# MSi001_board.net
KiCad netlist of a schematic drawn in EAGLE
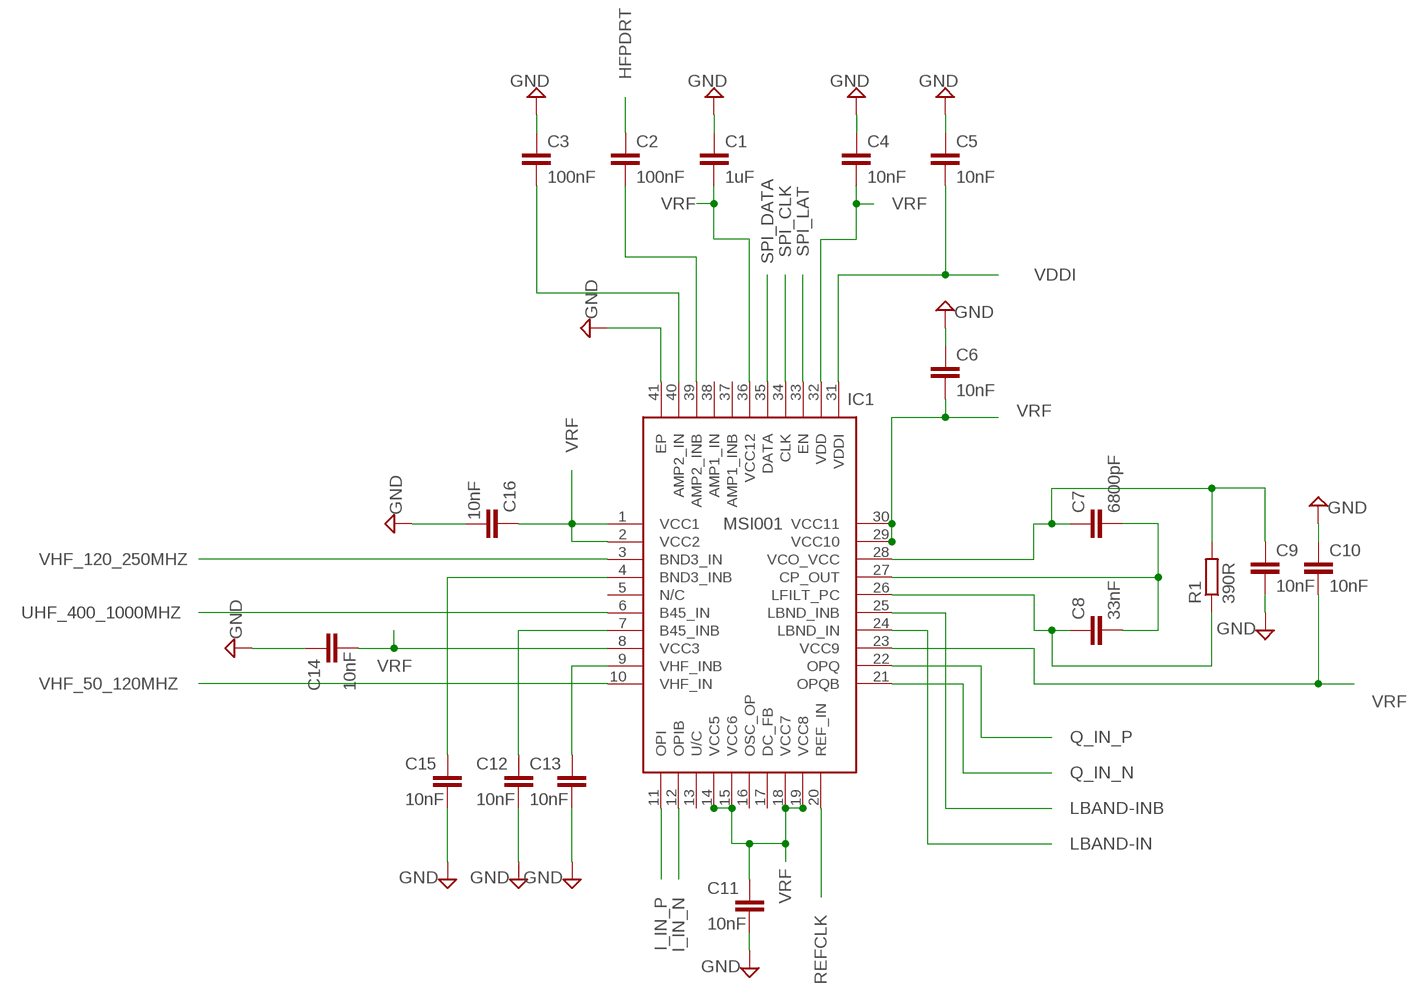
[diagram p0: schematic, sheet 1, part 1 of 2]
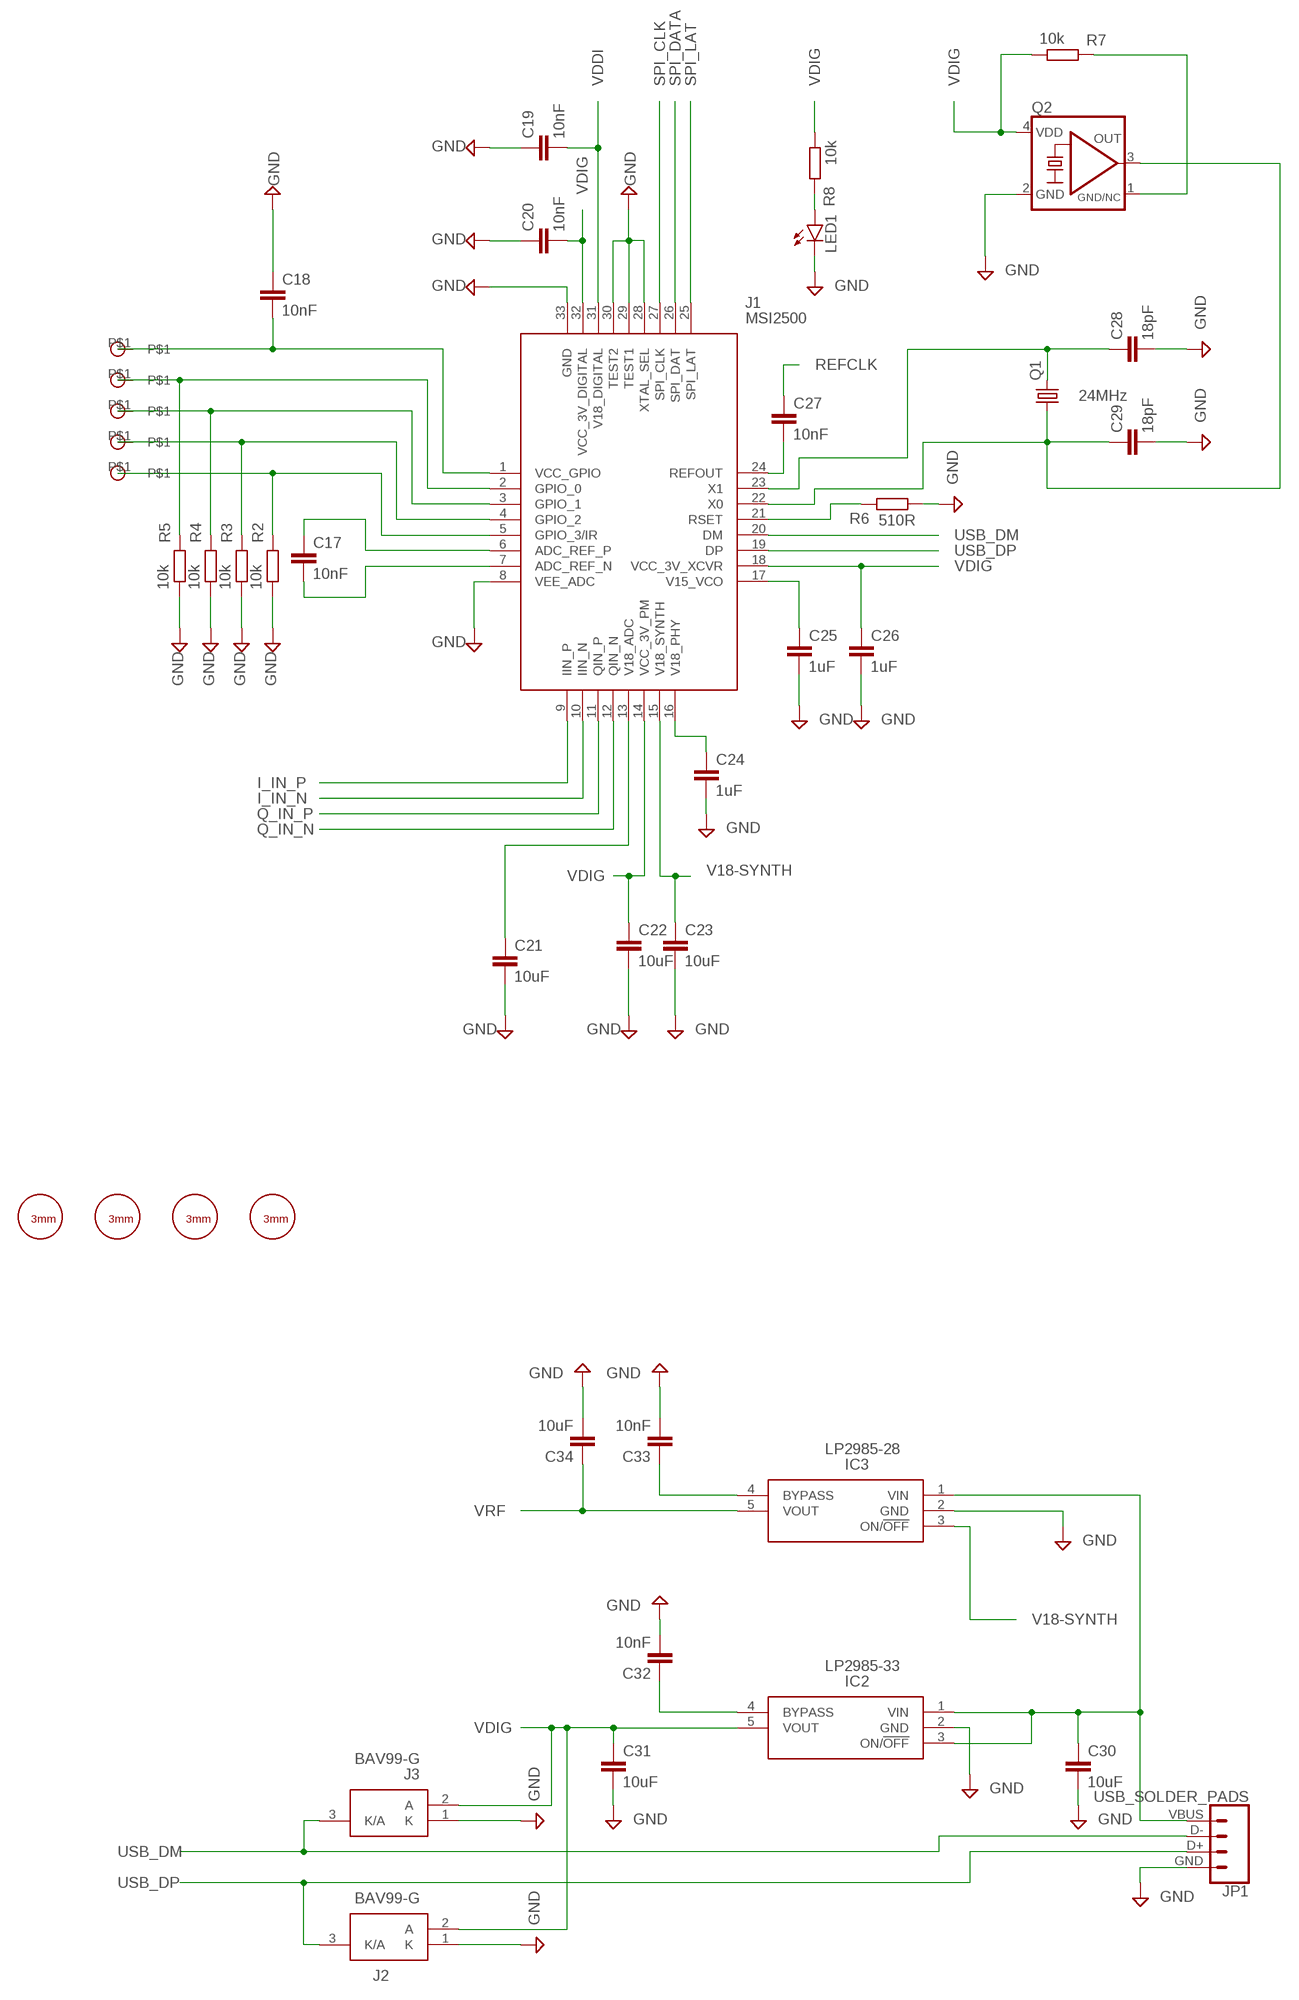
[diagram p1: schematic, sheet 1, part 2 of 2]

(export (version "E")
  (design (tool "Eeschema 10.0.6"))
  (components
    (comp (ref "C1")
      (value "1uF")
      (footprint "eagle-import:C0805K")
      (libsource (lib "eagle-import") (part "C-EUC0805K"))
    )
    (comp (ref "C2")
      (value "100nF")
      (footprint "eagle-import:C0603K")
      (libsource (lib "eagle-import") (part "C-EUC0603K"))
    )
    (comp (ref "C3")
      (value "100nF")
      (footprint "eagle-import:C0603K")
      (libsource (lib "eagle-import") (part "C-EUC0603K"))
    )
    (comp (ref "C4")
      (value "10nF")
      (footprint "eagle-import:C0603K")
      (libsource (lib "eagle-import") (part "C-EUC0603K"))
    )
    (comp (ref "C5")
      (value "10nF")
      (footprint "eagle-import:C0603K")
      (libsource (lib "eagle-import") (part "C-EUC0603K"))
    )
    (comp (ref "C6")
      (value "10nF")
      (footprint "eagle-import:C0603K")
      (libsource (lib "eagle-import") (part "C-EUC0603K"))
    )
    (comp (ref "C7")
      (value "6800pF")
      (footprint "eagle-import:C0603K")
      (libsource (lib "eagle-import") (part "C-EUC0603K"))
    )
    (comp (ref "C8")
      (value "33nF")
      (footprint "eagle-import:C0603K")
      (libsource (lib "eagle-import") (part "C-EUC0603K"))
    )
    (comp (ref "C9")
      (value "10nF")
      (footprint "eagle-import:C0603K")
      (libsource (lib "eagle-import") (part "C-EUC0603K"))
    )
    (comp (ref "C10")
      (value "10nF")
      (footprint "eagle-import:C0603K")
      (libsource (lib "eagle-import") (part "C-EUC0603K"))
    )
    (comp (ref "C11")
      (value "10nF")
      (footprint "eagle-import:C0603K")
      (libsource (lib "eagle-import") (part "C-EUC0603K"))
    )
    (comp (ref "C12")
      (value "10nF")
      (footprint "eagle-import:C0603K")
      (libsource (lib "eagle-import") (part "C-EUC0603K"))
    )
    (comp (ref "C13")
      (value "10nF")
      (footprint "eagle-import:C0603K")
      (libsource (lib "eagle-import") (part "C-EUC0603K"))
    )
    (comp (ref "C14")
      (value "10nF")
      (footprint "eagle-import:C0603K")
      (libsource (lib "eagle-import") (part "C-EUC0603K"))
    )
    (comp (ref "C15")
      (value "10nF")
      (footprint "eagle-import:C0603K")
      (libsource (lib "eagle-import") (part "C-EUC0603K"))
    )
    (comp (ref "C16")
      (value "10nF")
      (footprint "eagle-import:C0603K")
      (libsource (lib "eagle-import") (part "C-EUC0603K"))
    )
    (comp (ref "C17")
      (value "10nF")
      (footprint "eagle-import:C0603K")
      (libsource (lib "eagle-import") (part "C-EUC0603K"))
    )
    (comp (ref "C18")
      (value "10nF")
      (footprint "eagle-import:C0603K")
      (libsource (lib "eagle-import") (part "C-EUC0603K"))
    )
    (comp (ref "C19")
      (value "10nF")
      (footprint "eagle-import:C0603K")
      (libsource (lib "eagle-import") (part "C-EUC0603K"))
    )
    (comp (ref "C20")
      (value "10nF")
      (footprint "eagle-import:C0603K")
      (libsource (lib "eagle-import") (part "C-EUC0603K"))
    )
    (comp (ref "C21")
      (value "10uF")
      (footprint "eagle-import:C0805K")
      (libsource (lib "eagle-import") (part "C-EUC0805K"))
    )
    (comp (ref "C22")
      (value "10uF")
      (footprint "eagle-import:C0805K")
      (libsource (lib "eagle-import") (part "C-EUC0805K"))
    )
    (comp (ref "C23")
      (value "10uF")
      (footprint "eagle-import:C0805K")
      (libsource (lib "eagle-import") (part "C-EUC0805K"))
    )
    (comp (ref "C24")
      (value "1uF")
      (footprint "eagle-import:C0805K")
      (libsource (lib "eagle-import") (part "C-EUC0805K"))
    )
    (comp (ref "C25")
      (value "1uF")
      (footprint "eagle-import:C0805K")
      (libsource (lib "eagle-import") (part "C-EUC0805K"))
    )
    (comp (ref "C26")
      (value "1uF")
      (footprint "eagle-import:C0805K")
      (libsource (lib "eagle-import") (part "C-EUC0805K"))
    )
    (comp (ref "C27")
      (value "10nF")
      (footprint "eagle-import:C0603K")
      (libsource (lib "eagle-import") (part "C-EUC0603K"))
    )
    (comp (ref "C28")
      (value "18pF")
      (footprint "eagle-import:C0603K")
      (libsource (lib "eagle-import") (part "C-EUC0603K"))
    )
    (comp (ref "C29")
      (value "18pF")
      (footprint "eagle-import:C0603K")
      (libsource (lib "eagle-import") (part "C-EUC0603K"))
    )
    (comp (ref "C30")
      (value "10uF")
      (footprint "eagle-import:C0805K")
      (libsource (lib "eagle-import") (part "C-EUC0805K"))
    )
    (comp (ref "C31")
      (value "10uF")
      (footprint "eagle-import:C0805K")
      (libsource (lib "eagle-import") (part "C-EUC0805K"))
    )
    (comp (ref "C32")
      (value "10nF")
      (footprint "eagle-import:C0603K")
      (libsource (lib "eagle-import") (part "C-EUC0603K"))
    )
    (comp (ref "C33")
      (value "10nF")
      (footprint "eagle-import:C0603K")
      (libsource (lib "eagle-import") (part "C-EUC0603K"))
    )
    (comp (ref "C34")
      (value "10uF")
      (footprint "eagle-import:C0805K")
      (libsource (lib "eagle-import") (part "C-EUC0805K"))
    )
    (comp (ref "IC1")
      (value "MSI001")
      (footprint "eagle-import:QFN50P600X600X90-41N")
      (libsource (lib "eagle-import") (part "MSI001"))
    )
    (comp (ref "IC2")
      (value "LP2985-33")
      (footprint "eagle-import:SOT95P280X145-5N")
      (fields
        (field (name "ARROW_PART_NUMBER") "LP2985-30DBVR")
        (field (name "MOUSER_PART_NUMBER") "595-LP2985-30DBVR")
      )
      (libsource (lib "eagle-import") (part "LP2985-30DBVR"))
    )
    (comp (ref "IC3")
      (value "LP2985-28")
      (footprint "eagle-import:SOT95P280X145-5N")
      (fields
        (field (name "ARROW_PART_NUMBER") "LP2985-30DBVR")
        (field (name "MOUSER_PART_NUMBER") "595-LP2985-30DBVR")
      )
      (libsource (lib "eagle-import") (part "LP2985-30DBVR"))
    )
    (comp (ref "J1")
      (value "MSI2500")
      (footprint "eagle-import:QFN50P500X500X90-33N")
      (libsource (lib "eagle-import") (part "MSI2500"))
    )
    (comp (ref "J2")
      (value "BAV99-G")
      (footprint "eagle-import:SOT97P230X110-3N")
      (libsource (lib "eagle-import") (part "BAV99-G"))
    )
    (comp (ref "J3")
      (value "BAV99-G")
      (footprint "eagle-import:SOT97P230X110-3N")
      (libsource (lib "eagle-import") (part "BAV99-G"))
    )
    (comp (ref "JP1")
      (value "USB_SOLDER_PADS")
      (footprint "eagle-import:USB-SOLDER-PADS")
      (libsource (lib "eagle-import") (part "USB_SOLDER_PADS"))
    )
    (comp (ref "LED1")
      (value "LEDCHIPLED_0805")
      (footprint "eagle-import:CHIPLED_0805")
      (libsource (lib "eagle-import") (part "LEDCHIPLED_0805"))
    )
    (comp (ref "Q1")
      (value "24MHz")
      (footprint "eagle-import:HC49_S")
      (libsource (lib "eagle-import") (part "CRYSTALHC49S"))
    )
    (comp (ref "Q2")
      (value "KXO-TCXO-CMOS-83")
      (footprint "eagle-import:5.0X3.2_KXO-83-TCXO")
      (libsource (lib "eagle-import") (part "KXO-TCXO-CMOS-83"))
    )
    (comp (ref "R1")
      (value "390R")
      (footprint "eagle-import:R0603")
      (libsource (lib "eagle-import") (part "R-EU_R0603"))
    )
    (comp (ref "R2")
      (value "10k")
      (footprint "eagle-import:R0603")
      (libsource (lib "eagle-import") (part "R-EU_R0603"))
    )
    (comp (ref "R3")
      (value "10k")
      (footprint "eagle-import:R0603")
      (libsource (lib "eagle-import") (part "R-EU_R0603"))
    )
    (comp (ref "R4")
      (value "10k")
      (footprint "eagle-import:R0603")
      (libsource (lib "eagle-import") (part "R-EU_R0603"))
    )
    (comp (ref "R5")
      (value "10k")
      (footprint "eagle-import:R0603")
      (libsource (lib "eagle-import") (part "R-EU_R0603"))
    )
    (comp (ref "R6")
      (value "510R")
      (footprint "eagle-import:R0603")
      (libsource (lib "eagle-import") (part "R-EU_R0603"))
    )
    (comp (ref "R7")
      (value "10k")
      (footprint "eagle-import:R0603")
      (libsource (lib "eagle-import") (part "R-EU_R0603"))
    )
    (comp (ref "R8")
      (value "10k")
      (footprint "eagle-import:R0603")
      (libsource (lib "eagle-import") (part "R-EU_R0603"))
    )
    (comp (ref "U$1")
      (value "3MM_HOLE")
      (footprint "eagle-import:3MM_HOLE")
      (libsource (lib "eagle-import") (part "3MM_HOLE"))
    )
    (comp (ref "U$2")
      (value "SMD_PIN")
      (footprint "eagle-import:SMD_PIN")
      (libsource (lib "eagle-import") (part "SMD_PIN"))
    )
    (comp (ref "U$3")
      (value "SMD_PIN")
      (footprint "eagle-import:SMD_PIN")
      (libsource (lib "eagle-import") (part "SMD_PIN"))
    )
    (comp (ref "U$4")
      (value "SMD_PIN")
      (footprint "eagle-import:SMD_PIN")
      (libsource (lib "eagle-import") (part "SMD_PIN"))
    )
    (comp (ref "U$5")
      (value "SMD_PIN")
      (footprint "eagle-import:SMD_PIN")
      (libsource (lib "eagle-import") (part "SMD_PIN"))
    )
    (comp (ref "U$6")
      (value "3MM_HOLE")
      (footprint "eagle-import:3MM_HOLE")
      (libsource (lib "eagle-import") (part "3MM_HOLE"))
    )
    (comp (ref "U$7")
      (value "3MM_HOLE")
      (footprint "eagle-import:3MM_HOLE")
      (libsource (lib "eagle-import") (part "3MM_HOLE"))
    )
    (comp (ref "U$8")
      (value "3MM_HOLE")
      (footprint "eagle-import:3MM_HOLE")
      (libsource (lib "eagle-import") (part "3MM_HOLE"))
    )
    (comp (ref "VCC_GPIO")
      (value "SMD_PIN")
      (footprint "eagle-import:SMD_PIN")
      (libsource (lib "eagle-import") (part "SMD_PIN"))
    )
  )
  (nets
    (net (code "1") (name "/HFPDRT") (class "Default")
      (node (ref "C2") (pin "1") (pinfunction "1_1") (pintype "passive"))
    )
    (net (code "2") (name "/I_IN_N") (class "Default")
      (node (ref "IC1") (pin "12") (pinfunction "OPIB_12") (pintype "bidirectional"))
      (node (ref "J1") (pin "10") (pinfunction "IIN_N_10") (pintype "bidirectional"))
    )
    (net (code "3") (name "/I_IN_P") (class "Default")
      (node (ref "IC1") (pin "11") (pinfunction "OPI_11") (pintype "bidirectional"))
      (node (ref "J1") (pin "9") (pinfunction "IIN_P_9") (pintype "bidirectional"))
    )
    (net (code "4") (name "/LBAND-IN") (class "Default")
      (node (ref "IC1") (pin "24") (pinfunction "LBND_IN_24") (pintype "bidirectional"))
    )
    (net (code "5") (name "/LBAND-INB") (class "Default")
      (node (ref "IC1") (pin "25") (pinfunction "LBND_INB_25") (pintype "bidirectional"))
    )
    (net (code "6") (name "/Q_IN_N") (class "Default")
      (node (ref "IC1") (pin "21") (pinfunction "OPQB_21") (pintype "bidirectional"))
      (node (ref "J1") (pin "12") (pinfunction "QIN_N_12") (pintype "bidirectional"))
    )
    (net (code "7") (name "/Q_IN_P") (class "Default")
      (node (ref "IC1") (pin "22") (pinfunction "OPQ_22") (pintype "bidirectional"))
      (node (ref "J1") (pin "11") (pinfunction "QIN_P_11") (pintype "bidirectional"))
    )
    (net (code "8") (name "/REFCLK") (class "Default")
      (node (ref "C27") (pin "1") (pinfunction "1_1") (pintype "passive"))
      (node (ref "IC1") (pin "20") (pinfunction "REF_IN_20") (pintype "bidirectional"))
    )
    (net (code "9") (name "/SPI_CLK") (class "Default")
      (node (ref "IC1") (pin "34") (pinfunction "CLK_34") (pintype "bidirectional"))
      (node (ref "J1") (pin "27") (pinfunction "SPI_CLK_27") (pintype "bidirectional"))
    )
    (net (code "10") (name "/SPI_DATA") (class "Default")
      (node (ref "IC1") (pin "35") (pinfunction "DATA_35") (pintype "bidirectional"))
      (node (ref "J1") (pin "26") (pinfunction "SPI_DAT_26") (pintype "bidirectional"))
    )
    (net (code "11") (name "/SPI_LAT") (class "Default")
      (node (ref "IC1") (pin "33") (pinfunction "EN_33") (pintype "bidirectional"))
      (node (ref "J1") (pin "25") (pinfunction "SPI_LAT_25") (pintype "bidirectional"))
    )
    (net (code "12") (name "/UHF_400_1000MHZ") (class "Default")
      (node (ref "IC1") (pin "6") (pinfunction "B45_IN_6") (pintype "bidirectional"))
    )
    (net (code "13") (name "/USB_DM") (class "Default")
      (node (ref "J1") (pin "20") (pinfunction "DM_20") (pintype "bidirectional"))
      (node (ref "J3") (pin "3") (pinfunction "K/A_3") (pintype "bidirectional"))
      (node (ref "JP1") (pin "D-") (pinfunction "2_D-") (pintype "passive"))
    )
    (net (code "14") (name "/USB_DP") (class "Default")
      (node (ref "J1") (pin "19") (pinfunction "DP_19") (pintype "bidirectional"))
      (node (ref "J2") (pin "3") (pinfunction "K/A_3") (pintype "bidirectional"))
      (node (ref "JP1") (pin "D+") (pinfunction "3_D+") (pintype "passive"))
    )
    (net (code "15") (name "/V18-SYNTH") (class "Default")
      (node (ref "C23") (pin "1") (pinfunction "1_1") (pintype "passive"))
      (node (ref "IC3") (pin "3") (pinfunction "ON/~{OFF}_3") (pintype "bidirectional"))
      (node (ref "J1") (pin "15") (pinfunction "V18_SYNTH_15") (pintype "bidirectional"))
    )
    (net (code "16") (name "/VDDI") (class "Default")
      (node (ref "C19") (pin "2") (pinfunction "2_2") (pintype "passive"))
      (node (ref "C5") (pin "2") (pinfunction "2_2") (pintype "passive"))
      (node (ref "IC1") (pin "31") (pinfunction "VDDI_31") (pintype "bidirectional"))
      (node (ref "J1") (pin "31") (pinfunction "V18_DIGITAL_31") (pintype "bidirectional"))
    )
    (net (code "17") (name "/VDIG") (class "Default")
      (node (ref "C20") (pin "2") (pinfunction "2_2") (pintype "passive"))
      (node (ref "C22") (pin "1") (pinfunction "1_1") (pintype "passive"))
      (node (ref "C26") (pin "1") (pinfunction "1_1") (pintype "passive"))
      (node (ref "C31") (pin "1") (pinfunction "1_1") (pintype "passive"))
      (node (ref "IC2") (pin "5") (pinfunction "VOUT_5") (pintype "bidirectional"))
      (node (ref "J1") (pin "14") (pinfunction "VCC_3V_PM_14") (pintype "bidirectional"))
      (node (ref "J1") (pin "18") (pinfunction "VCC_3V_XCVR_18") (pintype "bidirectional"))
      (node (ref "J1") (pin "32") (pinfunction "VCC_3V_DIGITAL_32") (pintype "bidirectional"))
      (node (ref "J2") (pin "2") (pinfunction "A_2") (pintype "bidirectional"))
      (node (ref "J3") (pin "2") (pinfunction "A_2") (pintype "bidirectional"))
      (node (ref "Q2") (pin "4") (pinfunction "VDD_4") (pintype "power_in"))
      (node (ref "R7") (pin "1") (pinfunction "1_1") (pintype "passive"))
      (node (ref "R8") (pin "1") (pinfunction "1_1") (pintype "passive"))
    )
    (net (code "18") (name "/VHF_50_120MHZ") (class "Default")
      (node (ref "IC1") (pin "10") (pinfunction "VHF_IN_10") (pintype "bidirectional"))
    )
    (net (code "19") (name "/VHF_120_250MHZ") (class "Default")
      (node (ref "IC1") (pin "3") (pinfunction "BND3_IN_3") (pintype "bidirectional"))
    )
    (net (code "20") (name "/VRF") (class "Default")
      (node (ref "C1") (pin "2") (pinfunction "2_2") (pintype "passive"))
      (node (ref "C10") (pin "2") (pinfunction "2_2") (pintype "passive"))
      (node (ref "C11") (pin "1") (pinfunction "1_1") (pintype "passive"))
      (node (ref "C14") (pin "2") (pinfunction "2_2") (pintype "passive"))
      (node (ref "C16") (pin "1") (pinfunction "1_1") (pintype "passive"))
      (node (ref "C34") (pin "1") (pinfunction "1_1") (pintype "passive"))
      (node (ref "C4") (pin "2") (pinfunction "2_2") (pintype "passive"))
      (node (ref "C6") (pin "2") (pinfunction "2_2") (pintype "passive"))
      (node (ref "IC1") (pin "1") (pinfunction "VCC1_1") (pintype "bidirectional"))
      (node (ref "IC1") (pin "14") (pinfunction "VCC5_14") (pintype "bidirectional"))
      (node (ref "IC1") (pin "15") (pinfunction "VCC6_15") (pintype "bidirectional"))
      (node (ref "IC1") (pin "18") (pinfunction "VCC7_18") (pintype "bidirectional"))
      (node (ref "IC1") (pin "19") (pinfunction "VCC8_19") (pintype "bidirectional"))
      (node (ref "IC1") (pin "2") (pinfunction "VCC2_2") (pintype "bidirectional"))
      (node (ref "IC1") (pin "23") (pinfunction "VCC9_23") (pintype "bidirectional"))
      (node (ref "IC1") (pin "29") (pinfunction "VCC10_29") (pintype "bidirectional"))
      (node (ref "IC1") (pin "30") (pinfunction "VCC11_30") (pintype "bidirectional"))
      (node (ref "IC1") (pin "32") (pinfunction "VDD_32") (pintype "bidirectional"))
      (node (ref "IC1") (pin "36") (pinfunction "VCC12_36") (pintype "bidirectional"))
      (node (ref "IC1") (pin "8") (pinfunction "VCC3_8") (pintype "bidirectional"))
      (node (ref "IC3") (pin "5") (pinfunction "VOUT_5") (pintype "bidirectional"))
    )
    (net (code "21") (name "GND") (class "Default")
      (node (ref "C1") (pin "1") (pinfunction "1_1") (pintype "passive"))
      (node (ref "C10") (pin "1") (pinfunction "1_1") (pintype "passive"))
      (node (ref "C11") (pin "2") (pinfunction "2_2") (pintype "passive"))
      (node (ref "C12") (pin "2") (pinfunction "2_2") (pintype "passive"))
      (node (ref "C13") (pin "2") (pinfunction "2_2") (pintype "passive"))
      (node (ref "C14") (pin "1") (pinfunction "1_1") (pintype "passive"))
      (node (ref "C15") (pin "2") (pinfunction "2_2") (pintype "passive"))
      (node (ref "C16") (pin "2") (pinfunction "2_2") (pintype "passive"))
      (node (ref "C18") (pin "1") (pinfunction "1_1") (pintype "passive"))
      (node (ref "C19") (pin "1") (pinfunction "1_1") (pintype "passive"))
      (node (ref "C20") (pin "1") (pinfunction "1_1") (pintype "passive"))
      (node (ref "C21") (pin "2") (pinfunction "2_2") (pintype "passive"))
      (node (ref "C22") (pin "2") (pinfunction "2_2") (pintype "passive"))
      (node (ref "C23") (pin "2") (pinfunction "2_2") (pintype "passive"))
      (node (ref "C24") (pin "2") (pinfunction "2_2") (pintype "passive"))
      (node (ref "C25") (pin "2") (pinfunction "2_2") (pintype "passive"))
      (node (ref "C26") (pin "2") (pinfunction "2_2") (pintype "passive"))
      (node (ref "C28") (pin "2") (pinfunction "2_2") (pintype "passive"))
      (node (ref "C29") (pin "2") (pinfunction "2_2") (pintype "passive"))
      (node (ref "C3") (pin "1") (pinfunction "1_1") (pintype "passive"))
      (node (ref "C30") (pin "2") (pinfunction "2_2") (pintype "passive"))
      (node (ref "C31") (pin "2") (pinfunction "2_2") (pintype "passive"))
      (node (ref "C32") (pin "2") (pinfunction "2_2") (pintype "passive"))
      (node (ref "C33") (pin "2") (pinfunction "2_2") (pintype "passive"))
      (node (ref "C34") (pin "2") (pinfunction "2_2") (pintype "passive"))
      (node (ref "C4") (pin "1") (pinfunction "1_1") (pintype "passive"))
      (node (ref "C5") (pin "1") (pinfunction "1_1") (pintype "passive"))
      (node (ref "C6") (pin "1") (pinfunction "1_1") (pintype "passive"))
      (node (ref "C9") (pin "2") (pinfunction "2_2") (pintype "passive"))
      (node (ref "IC1") (pin "41") (pinfunction "EP_41") (pintype "bidirectional"))
      (node (ref "IC2") (pin "2") (pinfunction "GND_2") (pintype "bidirectional"))
      (node (ref "IC3") (pin "2") (pinfunction "GND_2") (pintype "bidirectional"))
      (node (ref "J1") (pin "28") (pinfunction "XTAL_SEL_28") (pintype "bidirectional"))
      (node (ref "J1") (pin "29") (pinfunction "TEST1_29") (pintype "bidirectional"))
      (node (ref "J1") (pin "30") (pinfunction "TEST2_30") (pintype "bidirectional"))
      (node (ref "J1") (pin "33") (pinfunction "GND_33") (pintype "bidirectional"))
      (node (ref "J1") (pin "8") (pinfunction "VEE_ADC_8") (pintype "bidirectional"))
      (node (ref "J2") (pin "1") (pinfunction "K_1") (pintype "bidirectional"))
      (node (ref "J3") (pin "1") (pinfunction "K_1") (pintype "bidirectional"))
      (node (ref "JP1") (pin "GND") (pinfunction "4_GND") (pintype "passive"))
      (node (ref "LED1") (pin "C") (pinfunction "C_C") (pintype "passive"))
      (node (ref "Q2") (pin "2") (pinfunction "GND_2") (pintype "power_in"))
      (node (ref "R2") (pin "1") (pinfunction "1_1") (pintype "passive"))
      (node (ref "R3") (pin "1") (pinfunction "1_1") (pintype "passive"))
      (node (ref "R4") (pin "1") (pinfunction "1_1") (pintype "passive"))
      (node (ref "R5") (pin "1") (pinfunction "1_1") (pintype "passive"))
      (node (ref "R6") (pin "1") (pinfunction "1_1") (pintype "passive"))
    )
    (net (code "22") (name "Net-(IC1-AMP2_IN)") (class "Default")
      (node (ref "C3") (pin "2") (pinfunction "2_2") (pintype "passive"))
      (node (ref "IC1") (pin "40") (pinfunction "AMP2_IN_40") (pintype "bidirectional"))
    )
    (net (code "23") (name "Net-(IC1-AMP2_INB)") (class "Default")
      (node (ref "C2") (pin "2") (pinfunction "2_2") (pintype "passive"))
      (node (ref "IC1") (pin "39") (pinfunction "AMP2_INB_39") (pintype "bidirectional"))
    )
    (net (code "24") (name "Net-(IC1-B45_INB)") (class "Default")
      (node (ref "C12") (pin "1") (pinfunction "1_1") (pintype "passive"))
      (node (ref "IC1") (pin "7") (pinfunction "B45_INB_7") (pintype "bidirectional"))
    )
    (net (code "25") (name "Net-(IC1-BND3_INB)") (class "Default")
      (node (ref "C15") (pin "1") (pinfunction "1_1") (pintype "passive"))
      (node (ref "IC1") (pin "4") (pinfunction "BND3_INB_4") (pintype "bidirectional"))
    )
    (net (code "26") (name "Net-(IC1-CP_OUT)") (class "Default")
      (node (ref "C7") (pin "2") (pinfunction "2_2") (pintype "passive"))
      (node (ref "C8") (pin "2") (pinfunction "2_2") (pintype "passive"))
      (node (ref "IC1") (pin "27") (pinfunction "CP_OUT_27") (pintype "bidirectional"))
    )
    (net (code "27") (name "Net-(IC1-LFILT_PC)") (class "Default")
      (node (ref "C8") (pin "1") (pinfunction "1_1") (pintype "passive"))
      (node (ref "IC1") (pin "26") (pinfunction "LFILT_PC_26") (pintype "bidirectional"))
      (node (ref "R1") (pin "1") (pinfunction "1_1") (pintype "passive"))
    )
    (net (code "28") (name "Net-(IC1-VCO_VCC)") (class "Default")
      (node (ref "C7") (pin "1") (pinfunction "1_1") (pintype "passive"))
      (node (ref "C9") (pin "1") (pinfunction "1_1") (pintype "passive"))
      (node (ref "IC1") (pin "28") (pinfunction "VCO_VCC_28") (pintype "bidirectional"))
      (node (ref "R1") (pin "2") (pinfunction "2_2") (pintype "passive"))
    )
    (net (code "29") (name "Net-(IC1-VHF_INB)") (class "Default")
      (node (ref "C13") (pin "1") (pinfunction "1_1") (pintype "passive"))
      (node (ref "IC1") (pin "9") (pinfunction "VHF_INB_9") (pintype "bidirectional"))
    )
    (net (code "30") (name "Net-(IC2-BYPASS)") (class "Default")
      (node (ref "C32") (pin "1") (pinfunction "1_1") (pintype "passive"))
      (node (ref "IC2") (pin "4") (pinfunction "BYPASS_4") (pintype "bidirectional"))
    )
    (net (code "31") (name "Net-(IC2-ON{slash}~{OFF})") (class "Default")
      (node (ref "C30") (pin "1") (pinfunction "1_1") (pintype "passive"))
      (node (ref "IC2") (pin "1") (pinfunction "VIN_1") (pintype "bidirectional"))
      (node (ref "IC2") (pin "3") (pinfunction "ON/~{OFF}_3") (pintype "bidirectional"))
      (node (ref "IC3") (pin "1") (pinfunction "VIN_1") (pintype "bidirectional"))
      (node (ref "JP1") (pin "VBUS") (pinfunction "1_VBUS") (pintype "passive"))
    )
    (net (code "32") (name "Net-(IC3-BYPASS)") (class "Default")
      (node (ref "C33") (pin "1") (pinfunction "1_1") (pintype "passive"))
      (node (ref "IC3") (pin "4") (pinfunction "BYPASS_4") (pintype "bidirectional"))
    )
    (net (code "33") (name "Net-(J1-ADC_REF_N)") (class "Default")
      (node (ref "C17") (pin "2") (pinfunction "2_2") (pintype "passive"))
      (node (ref "J1") (pin "7") (pinfunction "ADC_REF_N_7") (pintype "bidirectional"))
    )
    (net (code "34") (name "Net-(J1-ADC_REF_P)") (class "Default")
      (node (ref "C17") (pin "1") (pinfunction "1_1") (pintype "passive"))
      (node (ref "J1") (pin "6") (pinfunction "ADC_REF_P_6") (pintype "bidirectional"))
    )
    (net (code "35") (name "Net-(J1-GPIO_0)") (class "Default")
      (node (ref "J1") (pin "2") (pinfunction "GPIO_0_2") (pintype "bidirectional"))
      (node (ref "R5") (pin "2") (pinfunction "2_2") (pintype "passive"))
      (node (ref "U$2") (pin "P$1") (pinfunction "P$1_P$1") (pintype "bidirectional"))
    )
    (net (code "36") (name "Net-(J1-GPIO_1)") (class "Default")
      (node (ref "J1") (pin "3") (pinfunction "GPIO_1_3") (pintype "bidirectional"))
      (node (ref "R4") (pin "2") (pinfunction "2_2") (pintype "passive"))
      (node (ref "U$3") (pin "P$1") (pinfunction "P$1_P$1") (pintype "bidirectional"))
    )
    (net (code "37") (name "Net-(J1-GPIO_2)") (class "Default")
      (node (ref "J1") (pin "4") (pinfunction "GPIO_2_4") (pintype "bidirectional"))
      (node (ref "R3") (pin "2") (pinfunction "2_2") (pintype "passive"))
      (node (ref "U$4") (pin "P$1") (pinfunction "P$1_P$1") (pintype "bidirectional"))
    )
    (net (code "38") (name "Net-(J1-GPIO_3{slash}IR)") (class "Default")
      (node (ref "J1") (pin "5") (pinfunction "GPIO_3/IR_5") (pintype "bidirectional"))
      (node (ref "R2") (pin "2") (pinfunction "2_2") (pintype "passive"))
      (node (ref "U$5") (pin "P$1") (pinfunction "P$1_P$1") (pintype "bidirectional"))
    )
    (net (code "39") (name "Net-(J1-REFOUT)") (class "Default")
      (node (ref "C27") (pin "2") (pinfunction "2_2") (pintype "passive"))
      (node (ref "J1") (pin "24") (pinfunction "REFOUT_24") (pintype "bidirectional"))
    )
    (net (code "40") (name "Net-(J1-RSET)") (class "Default")
      (node (ref "J1") (pin "21") (pinfunction "RSET_21") (pintype "bidirectional"))
      (node (ref "R6") (pin "2") (pinfunction "2_2") (pintype "passive"))
    )
    (net (code "41") (name "Net-(J1-V15_VCO)") (class "Default")
      (node (ref "C25") (pin "1") (pinfunction "1_1") (pintype "passive"))
      (node (ref "J1") (pin "17") (pinfunction "V15_VCO_17") (pintype "bidirectional"))
    )
    (net (code "42") (name "Net-(J1-V18_ADC)") (class "Default")
      (node (ref "C21") (pin "1") (pinfunction "1_1") (pintype "passive"))
      (node (ref "J1") (pin "13") (pinfunction "V18_ADC_13") (pintype "bidirectional"))
    )
    (net (code "43") (name "Net-(J1-V18_PHY)") (class "Default")
      (node (ref "C24") (pin "1") (pinfunction "1_1") (pintype "passive"))
      (node (ref "J1") (pin "16") (pinfunction "V18_PHY_16") (pintype "bidirectional"))
    )
    (net (code "44") (name "Net-(J1-VCC_GPIO)") (class "Default")
      (node (ref "C18") (pin "2") (pinfunction "2_2") (pintype "passive"))
      (node (ref "J1") (pin "1") (pinfunction "VCC_GPIO_1") (pintype "bidirectional"))
      (node (ref "VCC_GPIO") (pin "P$1") (pinfunction "P$1_P$1") (pintype "bidirectional"))
    )
    (net (code "45") (name "Net-(J1-X0)") (class "Default")
      (node (ref "C29") (pin "1") (pinfunction "1_1") (pintype "passive"))
      (node (ref "J1") (pin "22") (pinfunction "X0_22") (pintype "bidirectional"))
      (node (ref "Q1") (pin "1") (pinfunction "1_1") (pintype "passive"))
      (node (ref "Q2") (pin "3") (pinfunction "OUT_3") (pintype "output"))
    )
    (net (code "46") (name "Net-(J1-X1)") (class "Default")
      (node (ref "C28") (pin "1") (pinfunction "1_1") (pintype "passive"))
      (node (ref "J1") (pin "23") (pinfunction "X1_23") (pintype "bidirectional"))
      (node (ref "Q1") (pin "2") (pinfunction "2_2") (pintype "passive"))
    )
    (net (code "47") (name "Net-(LED1-PadA)") (class "Default")
      (node (ref "LED1") (pin "A") (pinfunction "A_A") (pintype "passive"))
      (node (ref "R8") (pin "2") (pinfunction "2_2") (pintype "passive"))
    )
    (net (code "48") (name "Net-(Q2-GND{slash}NC)") (class "Default")
      (node (ref "Q2") (pin "1") (pinfunction "GND/NC_1") (pintype "power_in"))
      (node (ref "R7") (pin "2") (pinfunction "2_2") (pintype "passive"))
    )
    (net (code "49") (name "unconnected-(IC1-AMP1_IN-Pad38)") (class "Default")
      (node (ref "IC1") (pin "38") (pinfunction "AMP1_IN_38") (pintype "bidirectional"))
    )
    (net (code "50") (name "unconnected-(IC1-AMP1_INB-Pad37)") (class "Default")
      (node (ref "IC1") (pin "37") (pinfunction "AMP1_INB_37") (pintype "bidirectional"))
    )
    (net (code "51") (name "unconnected-(IC1-DC_FB-Pad17)") (class "Default")
      (node (ref "IC1") (pin "17") (pinfunction "DC_FB_17") (pintype "bidirectional"))
    )
    (net (code "52") (name "unconnected-(IC1-N{slash}C-Pad5)") (class "Default")
      (node (ref "IC1") (pin "5") (pinfunction "N/C_5") (pintype "no_connect"))
    )
    (net (code "53") (name "unconnected-(IC1-OSC_OP-Pad16)") (class "Default")
      (node (ref "IC1") (pin "16") (pinfunction "OSC_OP_16") (pintype "bidirectional"))
    )
    (net (code "54") (name "unconnected-(IC1-U{slash}C-Pad13)") (class "Default")
      (node (ref "IC1") (pin "13") (pinfunction "U/C_13") (pintype "bidirectional"))
    )
  )
)
